# switchotron-arduino-uno-shield-v1.net
KiCad netlist of a schematic drawn in EAGLE
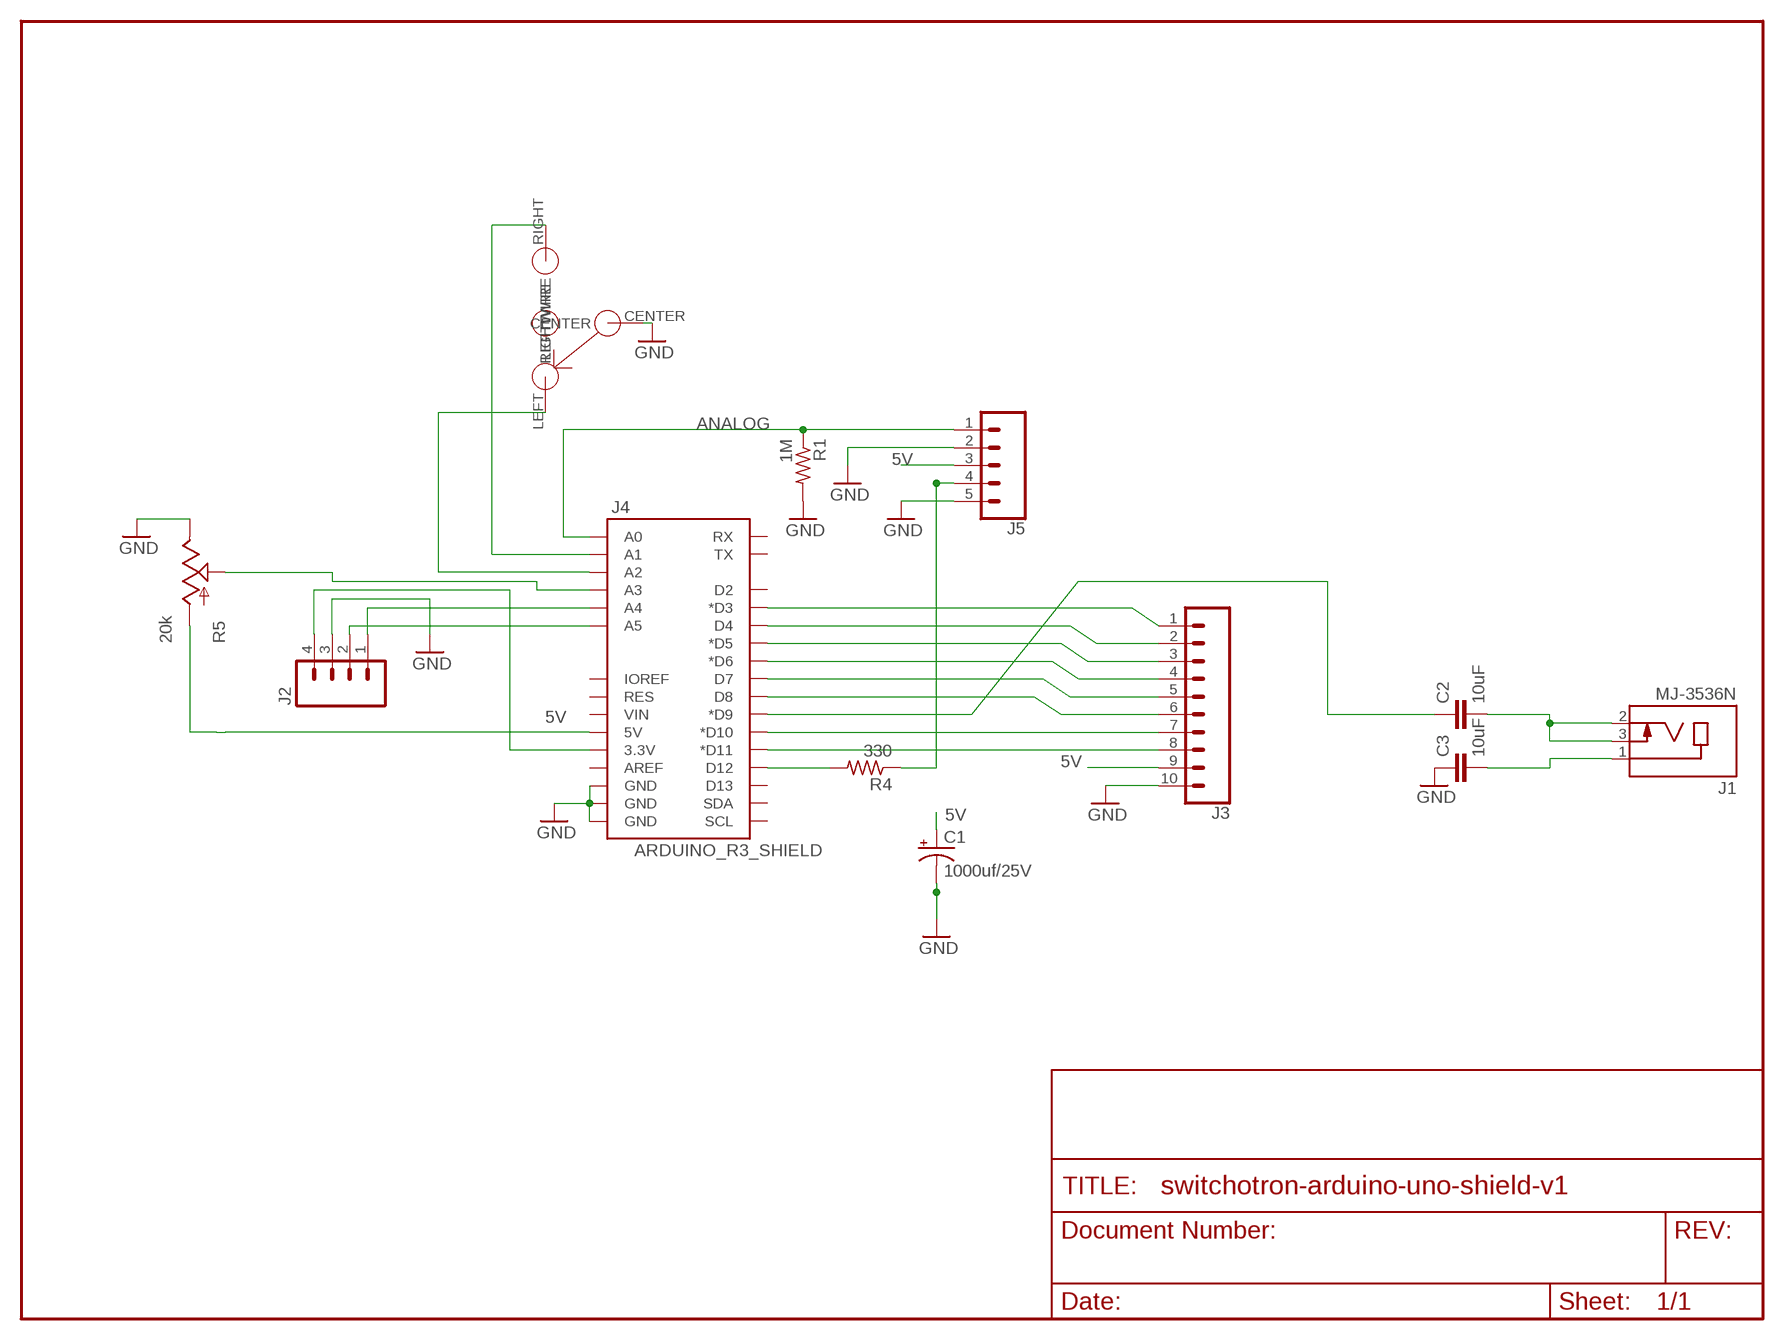
[diagram p0: schematic, sheet 1]

(export (version "E")
  (design (tool "Eeschema 10.0.6"))
  (components
    (comp (ref "C1")
      (value "1000uf/25V")
      (footprint "eagle-import:CPOL-RADIAL-1000UF-25V-KIT")
      (libsource (lib "eagle-import") (part "1000UF-25V(PTH)KIT"))
    )
    (comp (ref "C2")
      (value "10uF")
      (footprint "eagle-import:0805")
      (libsource (lib "eagle-import") (part "10UF-0805-10V-10%"))
    )
    (comp (ref "C3")
      (value "10uF")
      (footprint "eagle-import:0805")
      (libsource (lib "eagle-import") (part "10UF-0805-10V-10%"))
    )
    (comp (ref "J1")
      (value "MJ-3536N")
      (footprint "eagle-import:CUI_MJ-3536N")
      (fields (field (name "MANUFACTURER") "CUI INC"))
      (libsource (lib "eagle-import") (part "MJ-3536N"))
    )
    (comp (ref "J2")
      (value "M04PTH")
      (footprint "eagle-import:1X04")
      (libsource (lib "eagle-import") (part "M04PTH"))
    )
    (comp (ref "J3")
      (value "CONN_10\"")
      (footprint "eagle-import:1X10")
      (libsource (lib "eagle-import") (part "CONN_10{dblquote}"))
    )
    (comp (ref "J4")
      (value "ARDUINO_R3_SHIELD")
      (footprint "eagle-import:UNO_R3_SHIELD")
      (libsource (lib "eagle-import") (part "ARDUINO_R3_SHIELD"))
    )
    (comp (ref "J5")
      (value "CONN_05")
      (footprint "eagle-import:1X05")
      (libsource (lib "eagle-import") (part "CONN_05"))
    )
    (comp (ref "R1")
      (value "1M")
      (footprint "eagle-import:R0603")
      (libsource (lib "eagle-import") (part "R-US_R0603"))
    )
    (comp (ref "R4")
      (value "330")
      (footprint "eagle-import:R0603")
      (libsource (lib "eagle-import") (part "R-US_R0603"))
    )
    (comp (ref "R5")
      (value "20k")
      (footprint "eagle-import:ALPS_POT_KIT")
      (libsource (lib "eagle-import") (part "POTALPS-KIT"))
    )
    (comp (ref "SW3")
      (value "ON-OFF-ON-360-1013-ND")
      (footprint "eagle-import:360-1013-ND")
      (libsource (lib "eagle-import") (part "ON-OFF-ON-360-1013-ND"))
    )
  )
  (nets
    (net (code "1") (name "/5V") (class "Default")
      (node (ref "C1") (pin "+") (pinfunction "+_+") (pintype "passive"))
      (node (ref "J3") (pin "9") (pinfunction "9_9") (pintype "passive"))
      (node (ref "J4") (pin "5V") (pinfunction "5V_5V") (pintype "bidirectional"))
      (node (ref "J5") (pin "3") (pinfunction "3_3") (pintype "passive"))
      (node (ref "R5") (pin "P$3") (pinfunction "A_P$3") (pintype "passive"))
    )
    (net (code "2") (name "/ANALOG") (class "Default")
      (node (ref "J4") (pin "A0") (pinfunction "A0_A0") (pintype "bidirectional"))
      (node (ref "J5") (pin "1") (pinfunction "1_1") (pintype "passive"))
      (node (ref "R1") (pin "1") (pinfunction "1_1") (pintype "passive"))
    )
    (net (code "3") (name "GND") (class "Default")
      (node (ref "C1") (pin "-") (pinfunction "-_-") (pintype "passive"))
      (node (ref "C3") (pin "1") (pinfunction "1_1") (pintype "passive"))
      (node (ref "J2") (pin "3") (pinfunction "3_3") (pintype "passive"))
      (node (ref "J3") (pin "10") (pinfunction "10_10") (pintype "passive"))
      (node (ref "J4") (pin "GND@0") (pinfunction "GND_GND@0") (pintype "bidirectional"))
      (node (ref "J4") (pin "GND@1") (pinfunction "GND_GND@1") (pintype "bidirectional"))
      (node (ref "J4") (pin "GND@2") (pinfunction "GND_GND@2") (pintype "bidirectional"))
      (node (ref "J5") (pin "2") (pinfunction "2_2") (pintype "passive"))
      (node (ref "J5") (pin "5") (pinfunction "5_5") (pintype "passive"))
      (node (ref "R1") (pin "2") (pinfunction "2_2") (pintype "passive"))
      (node (ref "R5") (pin "P$1") (pinfunction "E_P$1") (pintype "passive"))
      (node (ref "SW3") (pin "CENTER") (pinfunction "CENTER_CENTER") (pintype "bidirectional"))
    )
    (net (code "4") (name "Net-(C2-Pad2)") (class "Default")
      (node (ref "C2") (pin "2") (pinfunction "2_2") (pintype "passive"))
      (node (ref "J1") (pin "2") (pinfunction "2_2") (pintype "passive"))
      (node (ref "J1") (pin "3") (pinfunction "3_3") (pintype "passive"))
    )
    (net (code "5") (name "Net-(C3-Pad2)") (class "Default")
      (node (ref "C3") (pin "2") (pinfunction "2_2") (pintype "passive"))
      (node (ref "J1") (pin "1") (pinfunction "1_1") (pintype "passive"))
    )
    (net (code "6") (name "Net-(J2-Pad1)") (class "Default")
      (node (ref "J2") (pin "1") (pinfunction "1_1") (pintype "passive"))
      (node (ref "J4") (pin "A4") (pinfunction "A4_A4") (pintype "bidirectional"))
    )
    (net (code "7") (name "Net-(J2-Pad2)") (class "Default")
      (node (ref "J2") (pin "2") (pinfunction "2_2") (pintype "passive"))
      (node (ref "J4") (pin "A5") (pinfunction "A5_A5") (pintype "bidirectional"))
    )
    (net (code "8") (name "Net-(J2-Pad4)") (class "Default")
      (node (ref "J2") (pin "4") (pinfunction "4_4") (pintype "passive"))
      (node (ref "J4") (pin "3.3V") (pinfunction "3.3V_3.3V") (pintype "bidirectional"))
    )
    (net (code "9") (name "Net-(J3-Pad2)") (class "Default")
      (node (ref "J3") (pin "2") (pinfunction "2_2") (pintype "passive"))
      (node (ref "J4") (pin "D4") (pinfunction "D4_D4") (pintype "bidirectional"))
    )
    (net (code "10") (name "Net-(J3-Pad5)") (class "Default")
      (node (ref "J3") (pin "5") (pinfunction "5_5") (pintype "passive"))
      (node (ref "J4") (pin "D7") (pinfunction "D7_D7") (pintype "bidirectional"))
    )
    (net (code "11") (name "Net-(J3-Pad6)") (class "Default")
      (node (ref "J3") (pin "6") (pinfunction "6_6") (pintype "passive"))
      (node (ref "J4") (pin "D8") (pinfunction "D8_D8") (pintype "bidirectional"))
    )
    (net (code "12") (name "Net-(J4-*D3)") (class "Default")
      (node (ref "J3") (pin "1") (pinfunction "1_1") (pintype "passive"))
      (node (ref "J4") (pin "D3") (pinfunction "*D3_D3") (pintype "bidirectional"))
    )
    (net (code "13") (name "Net-(J4-*D5)") (class "Default")
      (node (ref "J3") (pin "3") (pinfunction "3_3") (pintype "passive"))
      (node (ref "J4") (pin "D5") (pinfunction "*D5_D5") (pintype "bidirectional"))
    )
    (net (code "14") (name "Net-(J4-*D6)") (class "Default")
      (node (ref "J3") (pin "4") (pinfunction "4_4") (pintype "passive"))
      (node (ref "J4") (pin "D6") (pinfunction "*D6_D6") (pintype "bidirectional"))
    )
    (net (code "15") (name "Net-(J4-*D9)") (class "Default")
      (node (ref "C2") (pin "1") (pinfunction "1_1") (pintype "passive"))
      (node (ref "J4") (pin "D9") (pinfunction "*D9_D9") (pintype "bidirectional"))
    )
    (net (code "16") (name "Net-(J4-*D10)") (class "Default")
      (node (ref "J3") (pin "7") (pinfunction "7_7") (pintype "passive"))
      (node (ref "J4") (pin "D10") (pinfunction "*D10_D10") (pintype "bidirectional"))
    )
    (net (code "17") (name "Net-(J4-*D11)") (class "Default")
      (node (ref "J3") (pin "8") (pinfunction "8_8") (pintype "passive"))
      (node (ref "J4") (pin "D11") (pinfunction "*D11_D11") (pintype "bidirectional"))
    )
    (net (code "18") (name "Net-(J4-PadD12)") (class "Default")
      (node (ref "J4") (pin "D12") (pinfunction "D12_D12") (pintype "bidirectional"))
      (node (ref "R4") (pin "2") (pinfunction "2_2") (pintype "passive"))
    )
    (net (code "19") (name "Net-(J5-Pad4)") (class "Default")
      (node (ref "J5") (pin "4") (pinfunction "4_4") (pintype "passive"))
      (node (ref "R4") (pin "1") (pinfunction "1_1") (pintype "passive"))
    )
    (net (code "20") (name "Net-(R5-S)") (class "Default")
      (node (ref "J4") (pin "A3") (pinfunction "A3_A3") (pintype "bidirectional"))
      (node (ref "R5") (pin "P$2") (pinfunction "S_P$2") (pintype "passive"))
    )
    (net (code "21") (name "Net-(SW3-LEFTWIRE)") (class "Default")
      (node (ref "J4") (pin "A2") (pinfunction "A2_A2") (pintype "bidirectional"))
      (node (ref "SW3") (pin "LEFT") (pinfunction "LEFTWIRE_LEFT") (pintype "bidirectional"))
    )
    (net (code "22") (name "Net-(SW3-RIGHTWIRE)") (class "Default")
      (node (ref "J4") (pin "A1") (pinfunction "A1_A1") (pintype "bidirectional"))
      (node (ref "SW3") (pin "RIGHT") (pinfunction "RIGHTWIRE_RIGHT") (pintype "bidirectional"))
    )
    (net (code "23") (name "unconnected-(J4-PadAREF)") (class "Default")
      (node (ref "J4") (pin "AREF") (pinfunction "AREF_AREF") (pintype "bidirectional"))
    )
    (net (code "24") (name "unconnected-(J4-PadD2)") (class "Default")
      (node (ref "J4") (pin "D2") (pinfunction "D2_D2") (pintype "bidirectional"))
    )
    (net (code "25") (name "unconnected-(J4-PadD13)") (class "Default")
      (node (ref "J4") (pin "D13") (pinfunction "D13_D13") (pintype "bidirectional"))
    )
    (net (code "26") (name "unconnected-(J4-PadIOREF)") (class "Default")
      (node (ref "J4") (pin "IOREF") (pinfunction "IOREF_IOREF") (pintype "bidirectional"))
    )
    (net (code "27") (name "unconnected-(J4-PadRES)") (class "Default")
      (node (ref "J4") (pin "RES") (pinfunction "RES_RES") (pintype "bidirectional"))
    )
    (net (code "28") (name "unconnected-(J4-PadRX)") (class "Default")
      (node (ref "J4") (pin "RX") (pinfunction "RX_RX") (pintype "bidirectional"))
    )
    (net (code "29") (name "unconnected-(J4-PadSCL)") (class "Default")
      (node (ref "J4") (pin "SCL") (pinfunction "SCL_SCL") (pintype "bidirectional"))
    )
    (net (code "30") (name "unconnected-(J4-PadSDA)") (class "Default")
      (node (ref "J4") (pin "SDA") (pinfunction "SDA_SDA") (pintype "bidirectional"))
    )
    (net (code "31") (name "unconnected-(J4-PadTX)") (class "Default")
      (node (ref "J4") (pin "TX") (pinfunction "TX_TX") (pintype "bidirectional"))
    )
    (net (code "32") (name "unconnected-(J4-PadVIN)") (class "Default")
      (node (ref "J4") (pin "VIN") (pinfunction "VIN_VIN") (pintype "bidirectional"))
    )
  )
)
